# ambilight.net
KiCad netlist of a schematic drawn in EAGLE
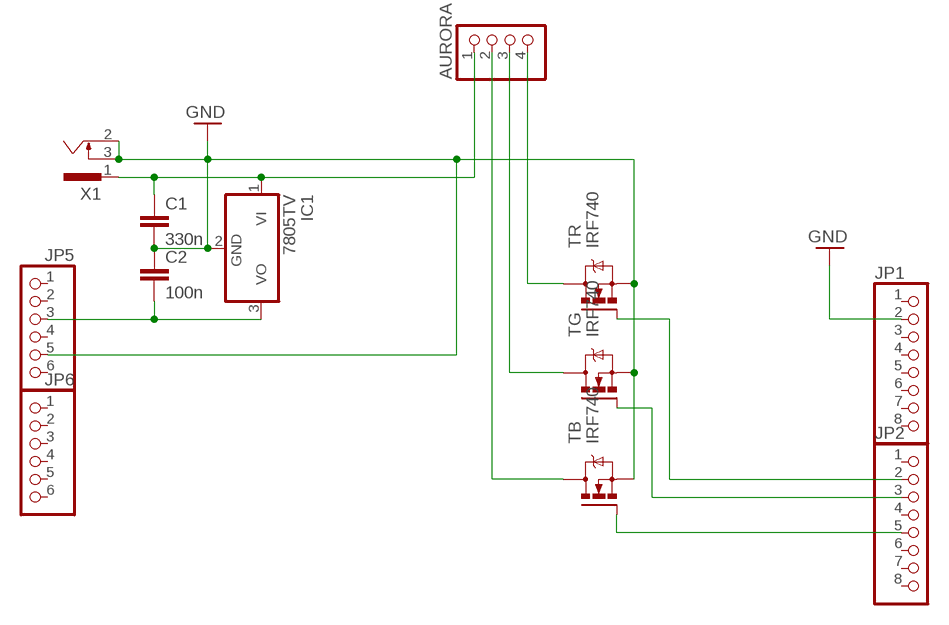
[diagram p0: schematic, sheet 1]

(export (version "E")
  (design (tool "Eeschema 10.0.6"))
  (components
    (comp (ref "AURORA")
      (value "PINHD-1X4")
      (footprint "eagle-import:1X04")
      (libsource (lib "eagle-import") (part "PINHD-1X4"))
    )
    (comp (ref "C1")
      (value "330n")
      (footprint "eagle-import:C025-050X050")
      (libsource (lib "eagle-import") (part "C-EU025-050X050"))
    )
    (comp (ref "C2")
      (value "100n")
      (footprint "eagle-import:C025-050X050")
      (libsource (lib "eagle-import") (part "C-EU025-050X050"))
    )
    (comp (ref "IC1")
      (value "7805TV")
      (footprint "eagle-import:TO220V")
      (libsource (lib "eagle-import") (part "78TV05"))
    )
    (comp (ref "JP1")
      (value "PINHD-1X8")
      (footprint "eagle-import:1X08")
      (libsource (lib "eagle-import") (part "PINHD-1X8"))
    )
    (comp (ref "JP2")
      (value "PINHD-1X8")
      (footprint "eagle-import:1X08")
      (libsource (lib "eagle-import") (part "PINHD-1X8"))
    )
    (comp (ref "JP5")
      (value "PINHD-1X6")
      (footprint "eagle-import:1X06")
      (libsource (lib "eagle-import") (part "PINHD-1X6"))
    )
    (comp (ref "JP6")
      (value "PINHD-1X6")
      (footprint "eagle-import:1X06")
      (libsource (lib "eagle-import") (part "PINHD-1X6"))
    )
    (comp (ref "TB")
      (value "IRF740")
      (footprint "eagle-import:TO220BV")
      (libsource (lib "eagle-import") (part "IRF740"))
    )
    (comp (ref "TG")
      (value "IRF740")
      (footprint "eagle-import:TO220BV")
      (libsource (lib "eagle-import") (part "IRF740"))
    )
    (comp (ref "TR")
      (value "IRF740")
      (footprint "eagle-import:TO220BV")
      (libsource (lib "eagle-import") (part "IRF740"))
    )
    (comp (ref "X1")
      (value "733980-62")
      (footprint "eagle-import:733980-62")
      (libsource (lib "eagle-import") (part "73398?0-62"))
    )
  )
  (nets
    (net (code "1") (name "GND") (class "Default")
      (node (ref "C1") (pin "2") (pinfunction "2_2") (pintype "passive"))
      (node (ref "C2") (pin "1") (pinfunction "1_1") (pintype "passive"))
      (node (ref "IC1") (pin "2") (pinfunction "GND_2") (pintype "passive"))
      (node (ref "JP1") (pin "2") (pinfunction "2_2") (pintype "passive"))
      (node (ref "JP5") (pin "5") (pinfunction "5_5") (pintype "passive"))
      (node (ref "TB") (pin "S") (pinfunction "S_S") (pintype "passive"))
      (node (ref "TG") (pin "S") (pinfunction "S_S") (pintype "passive"))
      (node (ref "TR") (pin "S") (pinfunction "S_S") (pintype "passive"))
      (node (ref "X1") (pin "2") (pinfunction "2_2") (pintype "passive"))
      (node (ref "X1") (pin "3") (pinfunction "3_3") (pintype "passive"))
    )
    (net (code "2") (name "Net-(AURORA-Pad2)") (class "Default")
      (node (ref "AURORA") (pin "2") (pinfunction "2_2") (pintype "passive"))
      (node (ref "TB") (pin "D") (pinfunction "D_D") (pintype "passive"))
    )
    (net (code "3") (name "Net-(AURORA-Pad3)") (class "Default")
      (node (ref "AURORA") (pin "3") (pinfunction "3_3") (pintype "passive"))
      (node (ref "TG") (pin "D") (pinfunction "D_D") (pintype "passive"))
    )
    (net (code "4") (name "Net-(AURORA-Pad4)") (class "Default")
      (node (ref "AURORA") (pin "4") (pinfunction "4_4") (pintype "passive"))
      (node (ref "TR") (pin "D") (pinfunction "D_D") (pintype "passive"))
    )
    (net (code "5") (name "Net-(IC1-VI)") (class "Default")
      (node (ref "AURORA") (pin "1") (pinfunction "1_1") (pintype "passive"))
      (node (ref "C1") (pin "1") (pinfunction "1_1") (pintype "passive"))
      (node (ref "IC1") (pin "1") (pinfunction "VI_1") (pintype "input"))
      (node (ref "X1") (pin "1") (pinfunction "1_1") (pintype "passive"))
    )
    (net (code "6") (name "Net-(IC1-VO)") (class "Default")
      (node (ref "C2") (pin "2") (pinfunction "2_2") (pintype "passive"))
      (node (ref "IC1") (pin "3") (pinfunction "VO_3") (pintype "passive"))
      (node (ref "JP5") (pin "3") (pinfunction "3_3") (pintype "passive"))
    )
    (net (code "7") (name "Net-(JP2-Pad2)") (class "Default")
      (node (ref "JP2") (pin "2") (pinfunction "2_2") (pintype "passive"))
      (node (ref "TR") (pin "G") (pinfunction "G_G") (pintype "passive"))
    )
    (net (code "8") (name "Net-(JP2-Pad3)") (class "Default")
      (node (ref "JP2") (pin "3") (pinfunction "3_3") (pintype "passive"))
      (node (ref "TG") (pin "G") (pinfunction "G_G") (pintype "passive"))
    )
    (net (code "9") (name "Net-(JP2-Pad5)") (class "Default")
      (node (ref "JP2") (pin "5") (pinfunction "5_5") (pintype "passive"))
      (node (ref "TB") (pin "G") (pinfunction "G_G") (pintype "passive"))
    )
    (net (code "10") (name "unconnected-(JP1-Pad1)") (class "Default")
      (node (ref "JP1") (pin "1") (pinfunction "1_1") (pintype "passive"))
    )
    (net (code "11") (name "unconnected-(JP1-Pad3)") (class "Default")
      (node (ref "JP1") (pin "3") (pinfunction "3_3") (pintype "passive"))
    )
    (net (code "12") (name "unconnected-(JP1-Pad4)") (class "Default")
      (node (ref "JP1") (pin "4") (pinfunction "4_4") (pintype "passive"))
    )
    (net (code "13") (name "unconnected-(JP1-Pad5)") (class "Default")
      (node (ref "JP1") (pin "5") (pinfunction "5_5") (pintype "passive"))
    )
    (net (code "14") (name "unconnected-(JP1-Pad6)") (class "Default")
      (node (ref "JP1") (pin "6") (pinfunction "6_6") (pintype "passive"))
    )
    (net (code "15") (name "unconnected-(JP1-Pad7)") (class "Default")
      (node (ref "JP1") (pin "7") (pinfunction "7_7") (pintype "passive"))
    )
    (net (code "16") (name "unconnected-(JP1-Pad8)") (class "Default")
      (node (ref "JP1") (pin "8") (pinfunction "8_8") (pintype "passive"))
    )
    (net (code "17") (name "unconnected-(JP2-Pad1)") (class "Default")
      (node (ref "JP2") (pin "1") (pinfunction "1_1") (pintype "passive"))
    )
    (net (code "18") (name "unconnected-(JP2-Pad4)") (class "Default")
      (node (ref "JP2") (pin "4") (pinfunction "4_4") (pintype "passive"))
    )
    (net (code "19") (name "unconnected-(JP2-Pad6)") (class "Default")
      (node (ref "JP2") (pin "6") (pinfunction "6_6") (pintype "passive"))
    )
    (net (code "20") (name "unconnected-(JP2-Pad7)") (class "Default")
      (node (ref "JP2") (pin "7") (pinfunction "7_7") (pintype "passive"))
    )
    (net (code "21") (name "unconnected-(JP2-Pad8)") (class "Default")
      (node (ref "JP2") (pin "8") (pinfunction "8_8") (pintype "passive"))
    )
    (net (code "22") (name "unconnected-(JP5-Pad1)") (class "Default")
      (node (ref "JP5") (pin "1") (pinfunction "1_1") (pintype "passive"))
    )
    (net (code "23") (name "unconnected-(JP5-Pad2)") (class "Default")
      (node (ref "JP5") (pin "2") (pinfunction "2_2") (pintype "passive"))
    )
    (net (code "24") (name "unconnected-(JP5-Pad4)") (class "Default")
      (node (ref "JP5") (pin "4") (pinfunction "4_4") (pintype "passive"))
    )
    (net (code "25") (name "unconnected-(JP5-Pad6)") (class "Default")
      (node (ref "JP5") (pin "6") (pinfunction "6_6") (pintype "passive"))
    )
    (net (code "26") (name "unconnected-(JP6-Pad1)") (class "Default")
      (node (ref "JP6") (pin "1") (pinfunction "1_1") (pintype "passive"))
    )
    (net (code "27") (name "unconnected-(JP6-Pad2)") (class "Default")
      (node (ref "JP6") (pin "2") (pinfunction "2_2") (pintype "passive"))
    )
    (net (code "28") (name "unconnected-(JP6-Pad3)") (class "Default")
      (node (ref "JP6") (pin "3") (pinfunction "3_3") (pintype "passive"))
    )
    (net (code "29") (name "unconnected-(JP6-Pad4)") (class "Default")
      (node (ref "JP6") (pin "4") (pinfunction "4_4") (pintype "passive"))
    )
    (net (code "30") (name "unconnected-(JP6-Pad5)") (class "Default")
      (node (ref "JP6") (pin "5") (pinfunction "5_5") (pintype "passive"))
    )
    (net (code "31") (name "unconnected-(JP6-Pad6)") (class "Default")
      (node (ref "JP6") (pin "6") (pinfunction "6_6") (pintype "passive"))
    )
  )
)
